# Rows.net
KiCad netlist of a schematic drawn in Altium Designer
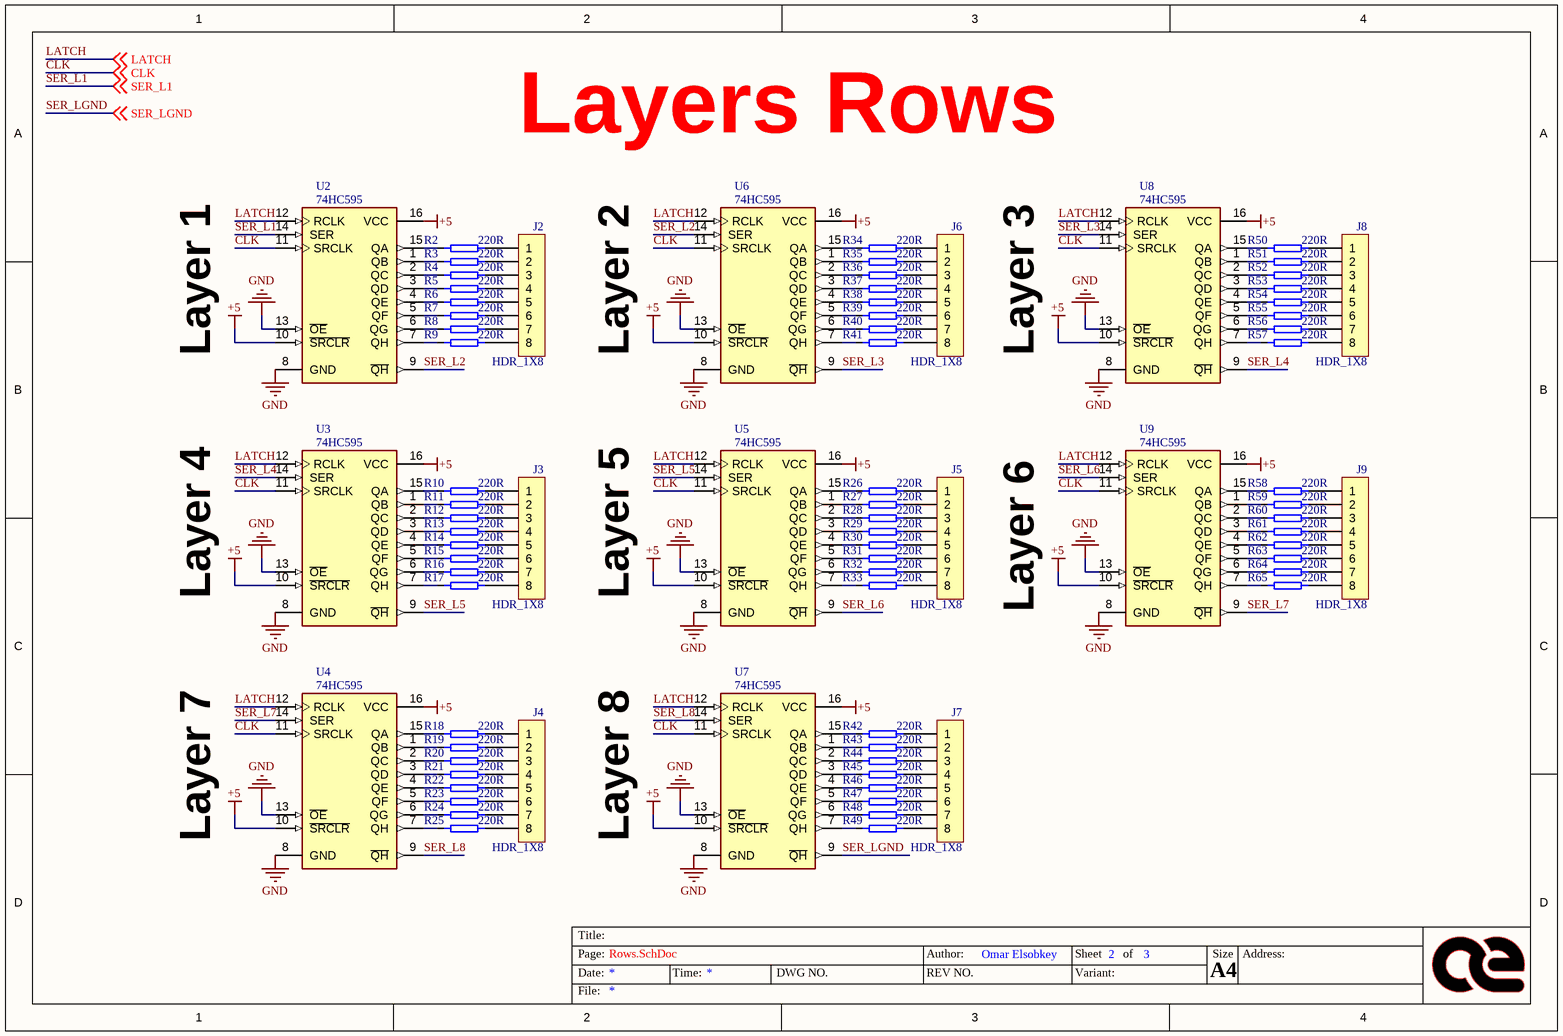
[diagram p0: Rows.SchDoc]

(export (version "E")
  (design (tool "Eeschema 10.0.6"))
  (components
    (comp (ref "J2")
      (value "HDR_1X8")
      (footprint "HDR_1X8_2.54MM")
      (description "Male Hedader 1x8")
      (libsource (lib "LED Cube") (part "HDR_1X8"))
    )
    (comp (ref "J3")
      (value "HDR_1X8")
      (footprint "HDR_1X8_2.54MM")
      (description "Male Hedader 1x8")
      (libsource (lib "LED Cube") (part "HDR_1X8"))
    )
    (comp (ref "J4")
      (value "HDR_1X8")
      (footprint "HDR_1X8_2.54MM")
      (description "Male Hedader 1x8")
      (libsource (lib "LED Cube") (part "HDR_1X8"))
    )
    (comp (ref "J5")
      (value "HDR_1X8")
      (footprint "HDR_1X8_2.54MM")
      (description "Male Hedader 1x8")
      (libsource (lib "LED Cube") (part "HDR_1X8"))
    )
    (comp (ref "J6")
      (value "HDR_1X8")
      (footprint "HDR_1X8_2.54MM")
      (description "Male Hedader 1x8")
      (libsource (lib "LED Cube") (part "HDR_1X8"))
    )
    (comp (ref "J7")
      (value "HDR_1X8")
      (footprint "HDR_1X8_2.54MM")
      (description "Male Hedader 1x8")
      (libsource (lib "LED Cube") (part "HDR_1X8"))
    )
    (comp (ref "J8")
      (value "HDR_1X8")
      (footprint "HDR_1X8_2.54MM")
      (description "Male Hedader 1x8")
      (libsource (lib "LED Cube") (part "HDR_1X8"))
    )
    (comp (ref "J9")
      (value "HDR_1X8")
      (footprint "HDR_1X8_2.54MM")
      (description "Male Hedader 1x8")
      (libsource (lib "LED Cube") (part "HDR_1X8"))
    )
    (comp (ref "R2") (value "220R") (footprint "R_AXIAL_0.3MM") (libsource (lib "LED Cube") (part "R 220")))
    (comp (ref "R3") (value "220R") (footprint "R_AXIAL_0.3MM") (libsource (lib "LED Cube") (part "R 220")))
    (comp (ref "R4") (value "220R") (footprint "R_AXIAL_0.3MM") (libsource (lib "LED Cube") (part "R 220")))
    (comp (ref "R5") (value "220R") (footprint "R_AXIAL_0.3MM") (libsource (lib "LED Cube") (part "R 220")))
    (comp (ref "R6") (value "220R") (footprint "R_AXIAL_0.3MM") (libsource (lib "LED Cube") (part "R 220")))
    (comp (ref "R7") (value "220R") (footprint "R_AXIAL_0.3MM") (libsource (lib "LED Cube") (part "R 220")))
    (comp (ref "R8") (value "220R") (footprint "R_AXIAL_0.3MM") (libsource (lib "LED Cube") (part "R 220")))
    (comp (ref "R9") (value "220R") (footprint "R_AXIAL_0.3MM") (libsource (lib "LED Cube") (part "R 220")))
    (comp (ref "R10") (value "220R") (footprint "R_AXIAL_0.3MM") (libsource (lib "LED Cube") (part "R 220")))
    (comp (ref "R11") (value "220R") (footprint "R_AXIAL_0.3MM") (libsource (lib "LED Cube") (part "R 220")))
    (comp (ref "R12") (value "220R") (footprint "R_AXIAL_0.3MM") (libsource (lib "LED Cube") (part "R 220")))
    (comp (ref "R13") (value "220R") (footprint "R_AXIAL_0.3MM") (libsource (lib "LED Cube") (part "R 220")))
    (comp (ref "R14") (value "220R") (footprint "R_AXIAL_0.3MM") (libsource (lib "LED Cube") (part "R 220")))
    (comp (ref "R15") (value "220R") (footprint "R_AXIAL_0.3MM") (libsource (lib "LED Cube") (part "R 220")))
    (comp (ref "R16") (value "220R") (footprint "R_AXIAL_0.3MM") (libsource (lib "LED Cube") (part "R 220")))
    (comp (ref "R17") (value "220R") (footprint "R_AXIAL_0.3MM") (libsource (lib "LED Cube") (part "R 220")))
    (comp (ref "R18") (value "220R") (footprint "R_AXIAL_0.3MM") (libsource (lib "LED Cube") (part "R 220")))
    (comp (ref "R19") (value "220R") (footprint "R_AXIAL_0.3MM") (libsource (lib "LED Cube") (part "R 220")))
    (comp (ref "R20") (value "220R") (footprint "R_AXIAL_0.3MM") (libsource (lib "LED Cube") (part "R 220")))
    (comp (ref "R21") (value "220R") (footprint "R_AXIAL_0.3MM") (libsource (lib "LED Cube") (part "R 220")))
    (comp (ref "R22") (value "220R") (footprint "R_AXIAL_0.3MM") (libsource (lib "LED Cube") (part "R 220")))
    (comp (ref "R23") (value "220R") (footprint "R_AXIAL_0.3MM") (libsource (lib "LED Cube") (part "R 220")))
    (comp (ref "R24") (value "220R") (footprint "R_AXIAL_0.3MM") (libsource (lib "LED Cube") (part "R 220")))
    (comp (ref "R25") (value "220R") (footprint "R_AXIAL_0.3MM") (libsource (lib "LED Cube") (part "R 220")))
    (comp (ref "R26") (value "220R") (footprint "R_AXIAL_0.3MM") (libsource (lib "LED Cube") (part "R 220")))
    (comp (ref "R27") (value "220R") (footprint "R_AXIAL_0.3MM") (libsource (lib "LED Cube") (part "R 220")))
    (comp (ref "R28") (value "220R") (footprint "R_AXIAL_0.3MM") (libsource (lib "LED Cube") (part "R 220")))
    (comp (ref "R29") (value "220R") (footprint "R_AXIAL_0.3MM") (libsource (lib "LED Cube") (part "R 220")))
    (comp (ref "R30") (value "220R") (footprint "R_AXIAL_0.3MM") (libsource (lib "LED Cube") (part "R 220")))
    (comp (ref "R31") (value "220R") (footprint "R_AXIAL_0.3MM") (libsource (lib "LED Cube") (part "R 220")))
    (comp (ref "R32") (value "220R") (footprint "R_AXIAL_0.3MM") (libsource (lib "LED Cube") (part "R 220")))
    (comp (ref "R33") (value "220R") (footprint "R_AXIAL_0.3MM") (libsource (lib "LED Cube") (part "R 220")))
    (comp (ref "R34") (value "220R") (footprint "R_AXIAL_0.3MM") (libsource (lib "LED Cube") (part "R 220")))
    (comp (ref "R35") (value "220R") (footprint "R_AXIAL_0.3MM") (libsource (lib "LED Cube") (part "R 220")))
    (comp (ref "R36") (value "220R") (footprint "R_AXIAL_0.3MM") (libsource (lib "LED Cube") (part "R 220")))
    (comp (ref "R37") (value "220R") (footprint "R_AXIAL_0.3MM") (libsource (lib "LED Cube") (part "R 220")))
    (comp (ref "R38") (value "220R") (footprint "R_AXIAL_0.3MM") (libsource (lib "LED Cube") (part "R 220")))
    (comp (ref "R39") (value "220R") (footprint "R_AXIAL_0.3MM") (libsource (lib "LED Cube") (part "R 220")))
    (comp (ref "R40") (value "220R") (footprint "R_AXIAL_0.3MM") (libsource (lib "LED Cube") (part "R 220")))
    (comp (ref "R41") (value "220R") (footprint "R_AXIAL_0.3MM") (libsource (lib "LED Cube") (part "R 220")))
    (comp (ref "R42") (value "220R") (footprint "R_AXIAL_0.3MM") (libsource (lib "LED Cube") (part "R 220")))
    (comp (ref "R43") (value "220R") (footprint "R_AXIAL_0.3MM") (libsource (lib "LED Cube") (part "R 220")))
    (comp (ref "R44") (value "220R") (footprint "R_AXIAL_0.3MM") (libsource (lib "LED Cube") (part "R 220")))
    (comp (ref "R45") (value "220R") (footprint "R_AXIAL_0.3MM") (libsource (lib "LED Cube") (part "R 220")))
    (comp (ref "R46") (value "220R") (footprint "R_AXIAL_0.3MM") (libsource (lib "LED Cube") (part "R 220")))
    (comp (ref "R47") (value "220R") (footprint "R_AXIAL_0.3MM") (libsource (lib "LED Cube") (part "R 220")))
    (comp (ref "R48") (value "220R") (footprint "R_AXIAL_0.3MM") (libsource (lib "LED Cube") (part "R 220")))
    (comp (ref "R49") (value "220R") (footprint "R_AXIAL_0.3MM") (libsource (lib "LED Cube") (part "R 220")))
    (comp (ref "R50") (value "220R") (footprint "R_AXIAL_0.3MM") (libsource (lib "LED Cube") (part "R 220")))
    (comp (ref "R51") (value "220R") (footprint "R_AXIAL_0.3MM") (libsource (lib "LED Cube") (part "R 220")))
    (comp (ref "R52") (value "220R") (footprint "R_AXIAL_0.3MM") (libsource (lib "LED Cube") (part "R 220")))
    (comp (ref "R53") (value "220R") (footprint "R_AXIAL_0.3MM") (libsource (lib "LED Cube") (part "R 220")))
    (comp (ref "R54") (value "220R") (footprint "R_AXIAL_0.3MM") (libsource (lib "LED Cube") (part "R 220")))
    (comp (ref "R55") (value "220R") (footprint "R_AXIAL_0.3MM") (libsource (lib "LED Cube") (part "R 220")))
    (comp (ref "R56") (value "220R") (footprint "R_AXIAL_0.3MM") (libsource (lib "LED Cube") (part "R 220")))
    (comp (ref "R57") (value "220R") (footprint "R_AXIAL_0.3MM") (libsource (lib "LED Cube") (part "R 220")))
    (comp (ref "R58") (value "220R") (footprint "R_AXIAL_0.3MM") (libsource (lib "LED Cube") (part "R 220")))
    (comp (ref "R59") (value "220R") (footprint "R_AXIAL_0.3MM") (libsource (lib "LED Cube") (part "R 220")))
    (comp (ref "R60") (value "220R") (footprint "R_AXIAL_0.3MM") (libsource (lib "LED Cube") (part "R 220")))
    (comp (ref "R61") (value "220R") (footprint "R_AXIAL_0.3MM") (libsource (lib "LED Cube") (part "R 220")))
    (comp (ref "R62") (value "220R") (footprint "R_AXIAL_0.3MM") (libsource (lib "LED Cube") (part "R 220")))
    (comp (ref "R63") (value "220R") (footprint "R_AXIAL_0.3MM") (libsource (lib "LED Cube") (part "R 220")))
    (comp (ref "R64") (value "220R") (footprint "R_AXIAL_0.3MM") (libsource (lib "LED Cube") (part "R 220")))
    (comp (ref "R65") (value "220R") (footprint "R_AXIAL_0.3MM") (libsource (lib "LED Cube") (part "R 220")))
    (comp (ref "U2")
      (value "74HC595")
      (footprint "DIP16")
      (description "Shift Register 74595")
      (fields (field (name "MP") "CD74HC595E"))
      (libsource (lib "LED Cube") (part "74HC595"))
    )
    (comp (ref "U3")
      (value "74HC595")
      (footprint "DIP16")
      (description "Shift Register 74595")
      (fields (field (name "MP") "CD74HC595E"))
      (libsource (lib "LED Cube") (part "74HC595"))
    )
    (comp (ref "U4")
      (value "74HC595")
      (footprint "DIP16")
      (description "Shift Register 74595")
      (fields (field (name "MP") "CD74HC595E"))
      (libsource (lib "LED Cube") (part "74HC595"))
    )
    (comp (ref "U5")
      (value "74HC595")
      (footprint "DIP16")
      (description "Shift Register 74595")
      (fields (field (name "MP") "CD74HC595E"))
      (libsource (lib "LED Cube") (part "74HC595"))
    )
    (comp (ref "U6")
      (value "74HC595")
      (footprint "DIP16")
      (description "Shift Register 74595")
      (fields (field (name "MP") "CD74HC595E"))
      (libsource (lib "LED Cube") (part "74HC595"))
    )
    (comp (ref "U7")
      (value "74HC595")
      (footprint "DIP16")
      (description "Shift Register 74595")
      (fields (field (name "MP") "CD74HC595E"))
      (libsource (lib "LED Cube") (part "74HC595"))
    )
    (comp (ref "U8")
      (value "74HC595")
      (footprint "DIP16")
      (description "Shift Register 74595")
      (fields (field (name "MP") "CD74HC595E"))
      (libsource (lib "LED Cube") (part "74HC595"))
    )
    (comp (ref "U9")
      (value "74HC595")
      (footprint "DIP16")
      (description "Shift Register 74595")
      (fields (field (name "MP") "CD74HC595E"))
      (libsource (lib "LED Cube") (part "74HC595"))
    )
  )
  (nets
    (net (code "1") (name "+5") (class "Default")
      (node (ref "U2") (pin "10") (pinfunction "~{SRCLR}_10") (pintype "input"))
      (node (ref "U2") (pin "16") (pinfunction "VCC_16") (pintype "power_in"))
      (node (ref "U3") (pin "10") (pinfunction "~{SRCLR}_10") (pintype "input"))
      (node (ref "U3") (pin "16") (pinfunction "VCC_16") (pintype "power_in"))
      (node (ref "U4") (pin "10") (pinfunction "~{SRCLR}_10") (pintype "input"))
      (node (ref "U4") (pin "16") (pinfunction "VCC_16") (pintype "power_in"))
      (node (ref "U5") (pin "10") (pinfunction "~{SRCLR}_10") (pintype "input"))
      (node (ref "U5") (pin "16") (pinfunction "VCC_16") (pintype "power_in"))
      (node (ref "U6") (pin "10") (pinfunction "~{SRCLR}_10") (pintype "input"))
      (node (ref "U6") (pin "16") (pinfunction "VCC_16") (pintype "power_in"))
      (node (ref "U7") (pin "10") (pinfunction "~{SRCLR}_10") (pintype "input"))
      (node (ref "U7") (pin "16") (pinfunction "VCC_16") (pintype "power_in"))
      (node (ref "U8") (pin "10") (pinfunction "~{SRCLR}_10") (pintype "input"))
      (node (ref "U8") (pin "16") (pinfunction "VCC_16") (pintype "power_in"))
      (node (ref "U9") (pin "10") (pinfunction "~{SRCLR}_10") (pintype "input"))
      (node (ref "U9") (pin "16") (pinfunction "VCC_16") (pintype "power_in"))
    )
    (net (code "2") (name "/SER_L2") (class "Default")
      (node (ref "U2") (pin "9") (pinfunction "~{QH}_9") (pintype "output"))
      (node (ref "U6") (pin "14") (pinfunction "SER_14") (pintype "input"))
    )
    (net (code "3") (name "/SER_L3") (class "Default")
      (node (ref "U6") (pin "9") (pinfunction "~{QH}_9") (pintype "output"))
      (node (ref "U8") (pin "14") (pinfunction "SER_14") (pintype "input"))
    )
    (net (code "4") (name "/SER_L4") (class "Default")
      (node (ref "U3") (pin "14") (pinfunction "SER_14") (pintype "input"))
      (node (ref "U8") (pin "9") (pinfunction "~{QH}_9") (pintype "output"))
    )
    (net (code "5") (name "/SER_L5") (class "Default")
      (node (ref "U3") (pin "9") (pinfunction "~{QH}_9") (pintype "output"))
      (node (ref "U5") (pin "14") (pinfunction "SER_14") (pintype "input"))
    )
    (net (code "6") (name "/SER_L6") (class "Default")
      (node (ref "U5") (pin "9") (pinfunction "~{QH}_9") (pintype "output"))
      (node (ref "U9") (pin "14") (pinfunction "SER_14") (pintype "input"))
    )
    (net (code "7") (name "/SER_L7") (class "Default")
      (node (ref "U4") (pin "14") (pinfunction "SER_14") (pintype "input"))
      (node (ref "U9") (pin "9") (pinfunction "~{QH}_9") (pintype "output"))
    )
    (net (code "8") (name "/SER_L8") (class "Default")
      (node (ref "U4") (pin "9") (pinfunction "~{QH}_9") (pintype "output"))
      (node (ref "U7") (pin "14") (pinfunction "SER_14") (pintype "input"))
    )
    (net (code "9") (name "CLK") (class "Default")
      (node (ref "U2") (pin "11") (pinfunction "SRCLK_11") (pintype "input"))
      (node (ref "U3") (pin "11") (pinfunction "SRCLK_11") (pintype "input"))
      (node (ref "U4") (pin "11") (pinfunction "SRCLK_11") (pintype "input"))
      (node (ref "U5") (pin "11") (pinfunction "SRCLK_11") (pintype "input"))
      (node (ref "U6") (pin "11") (pinfunction "SRCLK_11") (pintype "input"))
      (node (ref "U7") (pin "11") (pinfunction "SRCLK_11") (pintype "input"))
      (node (ref "U8") (pin "11") (pinfunction "SRCLK_11") (pintype "input"))
      (node (ref "U9") (pin "11") (pinfunction "SRCLK_11") (pintype "input"))
    )
    (net (code "10") (name "GND") (class "Default")
      (node (ref "U2") (pin "13") (pinfunction "~{OE}_13") (pintype "input"))
      (node (ref "U2") (pin "8") (pinfunction "GND_8") (pintype "power_in"))
      (node (ref "U3") (pin "13") (pinfunction "~{OE}_13") (pintype "input"))
      (node (ref "U3") (pin "8") (pinfunction "GND_8") (pintype "power_in"))
      (node (ref "U4") (pin "13") (pinfunction "~{OE}_13") (pintype "input"))
      (node (ref "U4") (pin "8") (pinfunction "GND_8") (pintype "power_in"))
      (node (ref "U5") (pin "13") (pinfunction "~{OE}_13") (pintype "input"))
      (node (ref "U5") (pin "8") (pinfunction "GND_8") (pintype "power_in"))
      (node (ref "U6") (pin "13") (pinfunction "~{OE}_13") (pintype "input"))
      (node (ref "U6") (pin "8") (pinfunction "GND_8") (pintype "power_in"))
      (node (ref "U7") (pin "13") (pinfunction "~{OE}_13") (pintype "input"))
      (node (ref "U7") (pin "8") (pinfunction "GND_8") (pintype "power_in"))
      (node (ref "U8") (pin "13") (pinfunction "~{OE}_13") (pintype "input"))
      (node (ref "U8") (pin "8") (pinfunction "GND_8") (pintype "power_in"))
      (node (ref "U9") (pin "13") (pinfunction "~{OE}_13") (pintype "input"))
      (node (ref "U9") (pin "8") (pinfunction "GND_8") (pintype "power_in"))
    )
    (net (code "11") (name "LATCH") (class "Default")
      (node (ref "U2") (pin "12") (pinfunction "RCLK_12") (pintype "input"))
      (node (ref "U3") (pin "12") (pinfunction "RCLK_12") (pintype "input"))
      (node (ref "U4") (pin "12") (pinfunction "RCLK_12") (pintype "input"))
      (node (ref "U5") (pin "12") (pinfunction "RCLK_12") (pintype "input"))
      (node (ref "U6") (pin "12") (pinfunction "RCLK_12") (pintype "input"))
      (node (ref "U7") (pin "12") (pinfunction "RCLK_12") (pintype "input"))
      (node (ref "U8") (pin "12") (pinfunction "RCLK_12") (pintype "input"))
      (node (ref "U9") (pin "12") (pinfunction "RCLK_12") (pintype "input"))
    )
    (net (code "12") (name "Net-(J2-Pad1)") (class "Default")
      (node (ref "J2") (pin "1") (pinfunction "1_1") (pintype "passive"))
      (node (ref "R2") (pin "2") (pinfunction "2_2") (pintype "passive"))
    )
    (net (code "13") (name "Net-(J2-Pad2)") (class "Default")
      (node (ref "J2") (pin "2") (pinfunction "2_2") (pintype "passive"))
      (node (ref "R3") (pin "2") (pinfunction "2_2") (pintype "passive"))
    )
    (net (code "14") (name "Net-(J2-Pad3)") (class "Default")
      (node (ref "J2") (pin "3") (pinfunction "3_3") (pintype "passive"))
      (node (ref "R4") (pin "2") (pinfunction "2_2") (pintype "passive"))
    )
    (net (code "15") (name "Net-(J2-Pad4)") (class "Default")
      (node (ref "J2") (pin "4") (pinfunction "4_4") (pintype "passive"))
      (node (ref "R5") (pin "2") (pinfunction "2_2") (pintype "passive"))
    )
    (net (code "16") (name "Net-(J2-Pad5)") (class "Default")
      (node (ref "J2") (pin "5") (pinfunction "5_5") (pintype "passive"))
      (node (ref "R6") (pin "2") (pinfunction "2_2") (pintype "passive"))
    )
    (net (code "17") (name "Net-(J2-Pad6)") (class "Default")
      (node (ref "J2") (pin "6") (pinfunction "6_6") (pintype "passive"))
      (node (ref "R7") (pin "2") (pinfunction "2_2") (pintype "passive"))
    )
    (net (code "18") (name "Net-(J2-Pad7)") (class "Default")
      (node (ref "J2") (pin "7") (pinfunction "7_7") (pintype "passive"))
      (node (ref "R8") (pin "2") (pinfunction "2_2") (pintype "passive"))
    )
    (net (code "19") (name "Net-(J2-Pad8)") (class "Default")
      (node (ref "J2") (pin "8") (pinfunction "8_8") (pintype "passive"))
      (node (ref "R9") (pin "2") (pinfunction "2_2") (pintype "passive"))
    )
    (net (code "20") (name "Net-(J3-Pad1)") (class "Default")
      (node (ref "J3") (pin "1") (pinfunction "1_1") (pintype "passive"))
      (node (ref "R10") (pin "2") (pinfunction "2_2") (pintype "passive"))
    )
    (net (code "21") (name "Net-(J3-Pad2)") (class "Default")
      (node (ref "J3") (pin "2") (pinfunction "2_2") (pintype "passive"))
      (node (ref "R11") (pin "2") (pinfunction "2_2") (pintype "passive"))
    )
    (net (code "22") (name "Net-(J3-Pad3)") (class "Default")
      (node (ref "J3") (pin "3") (pinfunction "3_3") (pintype "passive"))
      (node (ref "R12") (pin "2") (pinfunction "2_2") (pintype "passive"))
    )
    (net (code "23") (name "Net-(J3-Pad4)") (class "Default")
      (node (ref "J3") (pin "4") (pinfunction "4_4") (pintype "passive"))
      (node (ref "R13") (pin "2") (pinfunction "2_2") (pintype "passive"))
    )
    (net (code "24") (name "Net-(J3-Pad5)") (class "Default")
      (node (ref "J3") (pin "5") (pinfunction "5_5") (pintype "passive"))
      (node (ref "R14") (pin "2") (pinfunction "2_2") (pintype "passive"))
    )
    (net (code "25") (name "Net-(J3-Pad6)") (class "Default")
      (node (ref "J3") (pin "6") (pinfunction "6_6") (pintype "passive"))
      (node (ref "R15") (pin "2") (pinfunction "2_2") (pintype "passive"))
    )
    (net (code "26") (name "Net-(J3-Pad7)") (class "Default")
      (node (ref "J3") (pin "7") (pinfunction "7_7") (pintype "passive"))
      (node (ref "R16") (pin "2") (pinfunction "2_2") (pintype "passive"))
    )
    (net (code "27") (name "Net-(J3-Pad8)") (class "Default")
      (node (ref "J3") (pin "8") (pinfunction "8_8") (pintype "passive"))
      (node (ref "R17") (pin "2") (pinfunction "2_2") (pintype "passive"))
    )
    (net (code "28") (name "Net-(J4-Pad1)") (class "Default")
      (node (ref "J4") (pin "1") (pinfunction "1_1") (pintype "passive"))
      (node (ref "R18") (pin "2") (pinfunction "2_2") (pintype "passive"))
    )
    (net (code "29") (name "Net-(J4-Pad2)") (class "Default")
      (node (ref "J4") (pin "2") (pinfunction "2_2") (pintype "passive"))
      (node (ref "R19") (pin "2") (pinfunction "2_2") (pintype "passive"))
    )
    (net (code "30") (name "Net-(J4-Pad3)") (class "Default")
      (node (ref "J4") (pin "3") (pinfunction "3_3") (pintype "passive"))
      (node (ref "R20") (pin "2") (pinfunction "2_2") (pintype "passive"))
    )
    (net (code "31") (name "Net-(J4-Pad4)") (class "Default")
      (node (ref "J4") (pin "4") (pinfunction "4_4") (pintype "passive"))
      (node (ref "R21") (pin "2") (pinfunction "2_2") (pintype "passive"))
    )
    (net (code "32") (name "Net-(J4-Pad5)") (class "Default")
      (node (ref "J4") (pin "5") (pinfunction "5_5") (pintype "passive"))
      (node (ref "R22") (pin "2") (pinfunction "2_2") (pintype "passive"))
    )
    (net (code "33") (name "Net-(J4-Pad6)") (class "Default")
      (node (ref "J4") (pin "6") (pinfunction "6_6") (pintype "passive"))
      (node (ref "R23") (pin "2") (pinfunction "2_2") (pintype "passive"))
    )
    (net (code "34") (name "Net-(J4-Pad7)") (class "Default")
      (node (ref "J4") (pin "7") (pinfunction "7_7") (pintype "passive"))
      (node (ref "R24") (pin "2") (pinfunction "2_2") (pintype "passive"))
    )
    (net (code "35") (name "Net-(J4-Pad8)") (class "Default")
      (node (ref "J4") (pin "8") (pinfunction "8_8") (pintype "passive"))
      (node (ref "R25") (pin "2") (pinfunction "2_2") (pintype "passive"))
    )
    (net (code "36") (name "Net-(J5-Pad1)") (class "Default")
      (node (ref "J5") (pin "1") (pinfunction "1_1") (pintype "passive"))
      (node (ref "R26") (pin "2") (pinfunction "2_2") (pintype "passive"))
    )
    (net (code "37") (name "Net-(J5-Pad2)") (class "Default")
      (node (ref "J5") (pin "2") (pinfunction "2_2") (pintype "passive"))
      (node (ref "R27") (pin "2") (pinfunction "2_2") (pintype "passive"))
    )
    (net (code "38") (name "Net-(J5-Pad3)") (class "Default")
      (node (ref "J5") (pin "3") (pinfunction "3_3") (pintype "passive"))
      (node (ref "R28") (pin "2") (pinfunction "2_2") (pintype "passive"))
    )
    (net (code "39") (name "Net-(J5-Pad4)") (class "Default")
      (node (ref "J5") (pin "4") (pinfunction "4_4") (pintype "passive"))
      (node (ref "R29") (pin "2") (pinfunction "2_2") (pintype "passive"))
    )
    (net (code "40") (name "Net-(J5-Pad5)") (class "Default")
      (node (ref "J5") (pin "5") (pinfunction "5_5") (pintype "passive"))
      (node (ref "R30") (pin "2") (pinfunction "2_2") (pintype "passive"))
    )
    (net (code "41") (name "Net-(J5-Pad6)") (class "Default")
      (node (ref "J5") (pin "6") (pinfunction "6_6") (pintype "passive"))
      (node (ref "R31") (pin "2") (pinfunction "2_2") (pintype "passive"))
    )
    (net (code "42") (name "Net-(J5-Pad7)") (class "Default")
      (node (ref "J5") (pin "7") (pinfunction "7_7") (pintype "passive"))
      (node (ref "R32") (pin "2") (pinfunction "2_2") (pintype "passive"))
    )
    (net (code "43") (name "Net-(J5-Pad8)") (class "Default")
      (node (ref "J5") (pin "8") (pinfunction "8_8") (pintype "passive"))
      (node (ref "R33") (pin "2") (pinfunction "2_2") (pintype "passive"))
    )
    (net (code "44") (name "Net-(J6-Pad1)") (class "Default")
      (node (ref "J6") (pin "1") (pinfunction "1_1") (pintype "passive"))
      (node (ref "R34") (pin "2") (pinfunction "2_2") (pintype "passive"))
    )
    (net (code "45") (name "Net-(J6-Pad2)") (class "Default")
      (node (ref "J6") (pin "2") (pinfunction "2_2") (pintype "passive"))
      (node (ref "R35") (pin "2") (pinfunction "2_2") (pintype "passive"))
    )
    (net (code "46") (name "Net-(J6-Pad3)") (class "Default")
      (node (ref "J6") (pin "3") (pinfunction "3_3") (pintype "passive"))
      (node (ref "R36") (pin "2") (pinfunction "2_2") (pintype "passive"))
    )
    (net (code "47") (name "Net-(J6-Pad4)") (class "Default")
      (node (ref "J6") (pin "4") (pinfunction "4_4") (pintype "passive"))
      (node (ref "R37") (pin "2") (pinfunction "2_2") (pintype "passive"))
    )
    (net (code "48") (name "Net-(J6-Pad5)") (class "Default")
      (node (ref "J6") (pin "5") (pinfunction "5_5") (pintype "passive"))
      (node (ref "R38") (pin "2") (pinfunction "2_2") (pintype "passive"))
    )
    (net (code "49") (name "Net-(J6-Pad6)") (class "Default")
      (node (ref "J6") (pin "6") (pinfunction "6_6") (pintype "passive"))
      (node (ref "R39") (pin "2") (pinfunction "2_2") (pintype "passive"))
    )
    (net (code "50") (name "Net-(J6-Pad7)") (class "Default")
      (node (ref "J6") (pin "7") (pinfunction "7_7") (pintype "passive"))
      (node (ref "R40") (pin "2") (pinfunction "2_2") (pintype "passive"))
    )
    (net (code "51") (name "Net-(J6-Pad8)") (class "Default")
      (node (ref "J6") (pin "8") (pinfunction "8_8") (pintype "passive"))
      (node (ref "R41") (pin "2") (pinfunction "2_2") (pintype "passive"))
    )
    (net (code "52") (name "Net-(J7-Pad1)") (class "Default")
      (node (ref "J7") (pin "1") (pinfunction "1_1") (pintype "passive"))
      (node (ref "R42") (pin "2") (pinfunction "2_2") (pintype "passive"))
    )
    (net (code "53") (name "Net-(J7-Pad2)") (class "Default")
      (node (ref "J7") (pin "2") (pinfunction "2_2") (pintype "passive"))
      (node (ref "R43") (pin "2") (pinfunction "2_2") (pintype "passive"))
    )
    (net (code "54") (name "Net-(J7-Pad3)") (class "Default")
      (node (ref "J7") (pin "3") (pinfunction "3_3") (pintype "passive"))
      (node (ref "R44") (pin "2") (pinfunction "2_2") (pintype "passive"))
    )
    (net (code "55") (name "Net-(J7-Pad4)") (class "Default")
      (node (ref "J7") (pin "4") (pinfunction "4_4") (pintype "passive"))
      (node (ref "R45") (pin "2") (pinfunction "2_2") (pintype "passive"))
    )
    (net (code "56") (name "Net-(J7-Pad5)") (class "Default")
      (node (ref "J7") (pin "5") (pinfunction "5_5") (pintype "passive"))
      (node (ref "R46") (pin "2") (pinfunction "2_2") (pintype "passive"))
    )
    (net (code "57") (name "Net-(J7-Pad6)") (class "Default")
      (node (ref "J7") (pin "6") (pinfunction "6_6") (pintype "passive"))
      (node (ref "R47") (pin "2") (pinfunction "2_2") (pintype "passive"))
    )
    (net (code "58") (name "Net-(J7-Pad7)") (class "Default")
      (node (ref "J7") (pin "7") (pinfunction "7_7") (pintype "passive"))
      (node (ref "R48") (pin "2") (pinfunction "2_2") (pintype "passive"))
    )
    (net (code "59") (name "Net-(J7-Pad8)") (class "Default")
      (node (ref "J7") (pin "8") (pinfunction "8_8") (pintype "passive"))
      (node (ref "R49") (pin "2") (pinfunction "2_2") (pintype "passive"))
    )
    (net (code "60") (name "Net-(J8-Pad1)") (class "Default")
      (node (ref "J8") (pin "1") (pinfunction "1_1") (pintype "passive"))
      (node (ref "R50") (pin "2") (pinfunction "2_2") (pintype "passive"))
    )
    (net (code "61") (name "Net-(J8-Pad2)") (class "Default")
      (node (ref "J8") (pin "2") (pinfunction "2_2") (pintype "passive"))
      (node (ref "R51") (pin "2") (pinfunction "2_2") (pintype "passive"))
    )
    (net (code "62") (name "Net-(J8-Pad3)") (class "Default")
      (node (ref "J8") (pin "3") (pinfunction "3_3") (pintype "passive"))
      (node (ref "R52") (pin "2") (pinfunction "2_2") (pintype "passive"))
    )
    (net (code "63") (name "Net-(J8-Pad4)") (class "Default")
      (node (ref "J8") (pin "4") (pinfunction "4_4") (pintype "passive"))
      (node (ref "R53") (pin "2") (pinfunction "2_2") (pintype "passive"))
    )
    (net (code "64") (name "Net-(J8-Pad5)") (class "Default")
      (node (ref "J8") (pin "5") (pinfunction "5_5") (pintype "passive"))
      (node (ref "R54") (pin "2") (pinfunction "2_2") (pintype "passive"))
    )
    (net (code "65") (name "Net-(J8-Pad6)") (class "Default")
      (node (ref "J8") (pin "6") (pinfunction "6_6") (pintype "passive"))
      (node (ref "R55") (pin "2") (pinfunction "2_2") (pintype "passive"))
    )
    (net (code "66") (name "Net-(J8-Pad7)") (class "Default")
      (node (ref "J8") (pin "7") (pinfunction "7_7") (pintype "passive"))
      (node (ref "R56") (pin "2") (pinfunction "2_2") (pintype "passive"))
    )
    (net (code "67") (name "Net-(J8-Pad8)") (class "Default")
      (node (ref "J8") (pin "8") (pinfunction "8_8") (pintype "passive"))
      (node (ref "R57") (pin "2") (pinfunction "2_2") (pintype "passive"))
    )
    (net (code "68") (name "Net-(J9-Pad1)") (class "Default")
      (node (ref "J9") (pin "1") (pinfunction "1_1") (pintype "passive"))
      (node (ref "R58") (pin "2") (pinfunction "2_2") (pintype "passive"))
    )
    (net (code "69") (name "Net-(J9-Pad2)") (class "Default")
      (node (ref "J9") (pin "2") (pinfunction "2_2") (pintype "passive"))
      (node (ref "R59") (pin "2") (pinfunction "2_2") (pintype "passive"))
    )
    (net (code "70") (name "Net-(J9-Pad3)") (class "Default")
      (node (ref "J9") (pin "3") (pinfunction "3_3") (pintype "passive"))
      (node (ref "R60") (pin "2") (pinfunction "2_2") (pintype "passive"))
    )
    (net (code "71") (name "Net-(J9-Pad4)") (class "Default")
      (node (ref "J9") (pin "4") (pinfunction "4_4") (pintype "passive"))
      (node (ref "R61") (pin "2") (pinfunction "2_2") (pintype "passive"))
    )
    (net (code "72") (name "Net-(J9-Pad5)") (class "Default")
      (node (ref "J9") (pin "5") (pinfunction "5_5") (pintype "passive"))
      (node (ref "R62") (pin "2") (pinfunction "2_2") (pintype "passive"))
    )
    (net (code "73") (name "Net-(J9-Pad6)") (class "Default")
      (node (ref "J9") (pin "6") (pinfunction "6_6") (pintype "passive"))
      (node (ref "R63") (pin "2") (pinfunction "2_2") (pintype "passive"))
    )
    (net (code "74") (name "Net-(J9-Pad7)") (class "Default")
      (node (ref "J9") (pin "7") (pinfunction "7_7") (pintype "passive"))
      (node (ref "R64") (pin "2") (pinfunction "2_2") (pintype "passive"))
    )
    (net (code "75") (name "Net-(J9-Pad8)") (class "Default")
      (node (ref "J9") (pin "8") (pinfunction "8_8") (pintype "passive"))
      (node (ref "R65") (pin "2") (pinfunction "2_2") (pintype "passive"))
    )
    (net (code "76") (name "Net-(U2-QA)") (class "Default")
      (node (ref "R2") (pin "1") (pinfunction "1_1") (pintype "passive"))
      (node (ref "U2") (pin "15") (pinfunction "QA_15") (pintype "output"))
    )
    (net (code "77") (name "Net-(U2-QB)") (class "Default")
      (node (ref "R3") (pin "1") (pinfunction "1_1") (pintype "passive"))
      (node (ref "U2") (pin "1") (pinfunction "QB_1") (pintype "output"))
    )
    (net (code "78") (name "Net-(U2-QC)") (class "Default")
      (node (ref "R4") (pin "1") (pinfunction "1_1") (pintype "passive"))
      (node (ref "U2") (pin "2") (pinfunction "QC_2") (pintype "output"))
    )
    (net (code "79") (name "Net-(U2-QD)") (class "Default")
      (node (ref "R5") (pin "1") (pinfunction "1_1") (pintype "passive"))
      (node (ref "U2") (pin "3") (pinfunction "QD_3") (pintype "output"))
    )
    (net (code "80") (name "Net-(U2-QE)") (class "Default")
      (node (ref "R6") (pin "1") (pinfunction "1_1") (pintype "passive"))
      (node (ref "U2") (pin "4") (pinfunction "QE_4") (pintype "output"))
    )
    (net (code "81") (name "Net-(U2-QF)") (class "Default")
      (node (ref "R7") (pin "1") (pinfunction "1_1") (pintype "passive"))
      (node (ref "U2") (pin "5") (pinfunction "QF_5") (pintype "output"))
    )
    (net (code "82") (name "Net-(U2-QG)") (class "Default")
      (node (ref "R8") (pin "1") (pinfunction "1_1") (pintype "passive"))
      (node (ref "U2") (pin "6") (pinfunction "QG_6") (pintype "output"))
    )
    (net (code "83") (name "Net-(U2-QH)") (class "Default")
      (node (ref "R9") (pin "1") (pinfunction "1_1") (pintype "passive"))
      (node (ref "U2") (pin "7") (pinfunction "QH_7") (pintype "output"))
    )
    (net (code "84") (name "Net-(U3-QA)") (class "Default")
      (node (ref "R10") (pin "1") (pinfunction "1_1") (pintype "passive"))
      (node (ref "U3") (pin "15") (pinfunction "QA_15") (pintype "output"))
    )
    (net (code "85") (name "Net-(U3-QB)") (class "Default")
      (node (ref "R11") (pin "1") (pinfunction "1_1") (pintype "passive"))
      (node (ref "U3") (pin "1") (pinfunction "QB_1") (pintype "output"))
    )
    (net (code "86") (name "Net-(U3-QC)") (class "Default")
      (node (ref "R12") (pin "1") (pinfunction "1_1") (pintype "passive"))
      (node (ref "U3") (pin "2") (pinfunction "QC_2") (pintype "output"))
    )
    (net (code "87") (name "Net-(U3-QD)") (class "Default")
      (node (ref "R13") (pin "1") (pinfunction "1_1") (pintype "passive"))
      (node (ref "U3") (pin "3") (pinfunction "QD_3") (pintype "output"))
    )
    (net (code "88") (name "Net-(U3-QE)") (class "Default")
      (node (ref "R14") (pin "1") (pinfunction "1_1") (pintype "passive"))
      (node (ref "U3") (pin "4") (pinfunction "QE_4") (pintype "output"))
    )
    (net (code "89") (name "Net-(U3-QF)") (class "Default")
      (node (ref "R15") (pin "1") (pinfunction "1_1") (pintype "passive"))
      (node (ref "U3") (pin "5") (pinfunction "QF_5") (pintype "output"))
    )
    (net (code "90") (name "Net-(U3-QG)") (class "Default")
      (node (ref "R16") (pin "1") (pinfunction "1_1") (pintype "passive"))
      (node (ref "U3") (pin "6") (pinfunction "QG_6") (pintype "output"))
    )
    (net (code "91") (name "Net-(U3-QH)") (class "Default")
      (node (ref "R17") (pin "1") (pinfunction "1_1") (pintype "passive"))
      (node (ref "U3") (pin "7") (pinfunction "QH_7") (pintype "output"))
    )
    (net (code "92") (name "Net-(U4-QA)") (class "Default")
      (node (ref "R18") (pin "1") (pinfunction "1_1") (pintype "passive"))
      (node (ref "U4") (pin "15") (pinfunction "QA_15") (pintype "output"))
    )
    (net (code "93") (name "Net-(U4-QB)") (class "Default")
      (node (ref "R19") (pin "1") (pinfunction "1_1") (pintype "passive"))
      (node (ref "U4") (pin "1") (pinfunction "QB_1") (pintype "output"))
    )
    (net (code "94") (name "Net-(U4-QC)") (class "Default")
      (node (ref "R20") (pin "1") (pinfunction "1_1") (pintype "passive"))
      (node (ref "U4") (pin "2") (pinfunction "QC_2") (pintype "output"))
    )
    (net (code "95") (name "Net-(U4-QD)") (class "Default")
      (node (ref "R21") (pin "1") (pinfunction "1_1") (pintype "passive"))
      (node (ref "U4") (pin "3") (pinfunction "QD_3") (pintype "output"))
    )
    (net (code "96") (name "Net-(U4-QE)") (class "Default")
      (node (ref "R22") (pin "1") (pinfunction "1_1") (pintype "passive"))
      (node (ref "U4") (pin "4") (pinfunction "QE_4") (pintype "output"))
    )
    (net (code "97") (name "Net-(U4-QF)") (class "Default")
      (node (ref "R23") (pin "1") (pinfunction "1_1") (pintype "passive"))
      (node (ref "U4") (pin "5") (pinfunction "QF_5") (pintype "output"))
    )
    (net (code "98") (name "Net-(U4-QG)") (class "Default")
      (node (ref "R24") (pin "1") (pinfunction "1_1") (pintype "passive"))
      (node (ref "U4") (pin "6") (pinfunction "QG_6") (pintype "output"))
    )
    (net (code "99") (name "Net-(U4-QH)") (class "Default")
      (node (ref "R25") (pin "1") (pinfunction "1_1") (pintype "passive"))
      (node (ref "U4") (pin "7") (pinfunction "QH_7") (pintype "output"))
    )
    (net (code "100") (name "Net-(U5-QA)") (class "Default")
      (node (ref "R26") (pin "1") (pinfunction "1_1") (pintype "passive"))
      (node (ref "U5") (pin "15") (pinfunction "QA_15") (pintype "output"))
    )
    (net (code "101") (name "Net-(U5-QB)") (class "Default")
      (node (ref "R27") (pin "1") (pinfunction "1_1") (pintype "passive"))
      (node (ref "U5") (pin "1") (pinfunction "QB_1") (pintype "output"))
    )
    (net (code "102") (name "Net-(U5-QC)") (class "Default")
      (node (ref "R28") (pin "1") (pinfunction "1_1") (pintype "passive"))
      (node (ref "U5") (pin "2") (pinfunction "QC_2") (pintype "output"))
    )
    (net (code "103") (name "Net-(U5-QD)") (class "Default")
      (node (ref "R29") (pin "1") (pinfunction "1_1") (pintype "passive"))
      (node (ref "U5") (pin "3") (pinfunction "QD_3") (pintype "output"))
    )
    (net (code "104") (name "Net-(U5-QE)") (class "Default")
      (node (ref "R30") (pin "1") (pinfunction "1_1") (pintype "passive"))
      (node (ref "U5") (pin "4") (pinfunction "QE_4") (pintype "output"))
    )
    (net (code "105") (name "Net-(U5-QF)") (class "Default")
      (node (ref "R31") (pin "1") (pinfunction "1_1") (pintype "passive"))
      (node (ref "U5") (pin "5") (pinfunction "QF_5") (pintype "output"))
    )
    (net (code "106") (name "Net-(U5-QG)") (class "Default")
      (node (ref "R32") (pin "1") (pinfunction "1_1") (pintype "passive"))
      (node (ref "U5") (pin "6") (pinfunction "QG_6") (pintype "output"))
    )
    (net (code "107") (name "Net-(U5-QH)") (class "Default")
      (node (ref "R33") (pin "1") (pinfunction "1_1") (pintype "passive"))
      (node (ref "U5") (pin "7") (pinfunction "QH_7") (pintype "output"))
    )
    (net (code "108") (name "Net-(U6-QA)") (class "Default")
      (node (ref "R34") (pin "1") (pinfunction "1_1") (pintype "passive"))
      (node (ref "U6") (pin "15") (pinfunction "QA_15") (pintype "output"))
    )
    (net (code "109") (name "Net-(U6-QB)") (class "Default")
      (node (ref "R35") (pin "1") (pinfunction "1_1") (pintype "passive"))
      (node (ref "U6") (pin "1") (pinfunction "QB_1") (pintype "output"))
    )
    (net (code "110") (name "Net-(U6-QC)") (class "Default")
      (node (ref "R36") (pin "1") (pinfunction "1_1") (pintype "passive"))
      (node (ref "U6") (pin "2") (pinfunction "QC_2") (pintype "output"))
    )
    (net (code "111") (name "Net-(U6-QD)") (class "Default")
      (node (ref "R37") (pin "1") (pinfunction "1_1") (pintype "passive"))
      (node (ref "U6") (pin "3") (pinfunction "QD_3") (pintype "output"))
    )
    (net (code "112") (name "Net-(U6-QE)") (class "Default")
      (node (ref "R38") (pin "1") (pinfunction "1_1") (pintype "passive"))
      (node (ref "U6") (pin "4") (pinfunction "QE_4") (pintype "output"))
    )
    (net (code "113") (name "Net-(U6-QF)") (class "Default")
      (node (ref "R39") (pin "1") (pinfunction "1_1") (pintype "passive"))
      (node (ref "U6") (pin "5") (pinfunction "QF_5") (pintype "output"))
    )
    (net (code "114") (name "Net-(U6-QG)") (class "Default")
      (node (ref "R40") (pin "1") (pinfunction "1_1") (pintype "passive"))
      (node (ref "U6") (pin "6") (pinfunction "QG_6") (pintype "output"))
    )
    (net (code "115") (name "Net-(U6-QH)") (class "Default")
      (node (ref "R41") (pin "1") (pinfunction "1_1") (pintype "passive"))
      (node (ref "U6") (pin "7") (pinfunction "QH_7") (pintype "output"))
    )
    (net (code "116") (name "Net-(U7-QA)") (class "Default")
      (node (ref "R42") (pin "1") (pinfunction "1_1") (pintype "passive"))
      (node (ref "U7") (pin "15") (pinfunction "QA_15") (pintype "output"))
    )
    (net (code "117") (name "Net-(U7-QB)") (class "Default")
      (node (ref "R43") (pin "1") (pinfunction "1_1") (pintype "passive"))
      (node (ref "U7") (pin "1") (pinfunction "QB_1") (pintype "output"))
    )
    (net (code "118") (name "Net-(U7-QC)") (class "Default")
      (node (ref "R44") (pin "1") (pinfunction "1_1") (pintype "passive"))
      (node (ref "U7") (pin "2") (pinfunction "QC_2") (pintype "output"))
    )
    (net (code "119") (name "Net-(U7-QD)") (class "Default")
      (node (ref "R45") (pin "1") (pinfunction "1_1") (pintype "passive"))
      (node (ref "U7") (pin "3") (pinfunction "QD_3") (pintype "output"))
    )
    (net (code "120") (name "Net-(U7-QE)") (class "Default")
      (node (ref "R46") (pin "1") (pinfunction "1_1") (pintype "passive"))
      (node (ref "U7") (pin "4") (pinfunction "QE_4") (pintype "output"))
    )
    (net (code "121") (name "Net-(U7-QF)") (class "Default")
      (node (ref "R47") (pin "1") (pinfunction "1_1") (pintype "passive"))
      (node (ref "U7") (pin "5") (pinfunction "QF_5") (pintype "output"))
    )
    (net (code "122") (name "Net-(U7-QG)") (class "Default")
      (node (ref "R48") (pin "1") (pinfunction "1_1") (pintype "passive"))
      (node (ref "U7") (pin "6") (pinfunction "QG_6") (pintype "output"))
    )
    (net (code "123") (name "Net-(U7-QH)") (class "Default")
      (node (ref "R49") (pin "1") (pinfunction "1_1") (pintype "passive"))
      (node (ref "U7") (pin "7") (pinfunction "QH_7") (pintype "output"))
    )
    (net (code "124") (name "Net-(U8-QA)") (class "Default")
      (node (ref "R50") (pin "1") (pinfunction "1_1") (pintype "passive"))
      (node (ref "U8") (pin "15") (pinfunction "QA_15") (pintype "output"))
    )
    (net (code "125") (name "Net-(U8-QB)") (class "Default")
      (node (ref "R51") (pin "1") (pinfunction "1_1") (pintype "passive"))
      (node (ref "U8") (pin "1") (pinfunction "QB_1") (pintype "output"))
    )
    (net (code "126") (name "Net-(U8-QC)") (class "Default")
      (node (ref "R52") (pin "1") (pinfunction "1_1") (pintype "passive"))
      (node (ref "U8") (pin "2") (pinfunction "QC_2") (pintype "output"))
    )
    (net (code "127") (name "Net-(U8-QD)") (class "Default")
      (node (ref "R53") (pin "1") (pinfunction "1_1") (pintype "passive"))
      (node (ref "U8") (pin "3") (pinfunction "QD_3") (pintype "output"))
    )
    (net (code "128") (name "Net-(U8-QE)") (class "Default")
      (node (ref "R54") (pin "1") (pinfunction "1_1") (pintype "passive"))
      (node (ref "U8") (pin "4") (pinfunction "QE_4") (pintype "output"))
    )
    (net (code "129") (name "Net-(U8-QF)") (class "Default")
      (node (ref "R55") (pin "1") (pinfunction "1_1") (pintype "passive"))
      (node (ref "U8") (pin "5") (pinfunction "QF_5") (pintype "output"))
    )
    (net (code "130") (name "Net-(U8-QG)") (class "Default")
      (node (ref "R56") (pin "1") (pinfunction "1_1") (pintype "passive"))
      (node (ref "U8") (pin "6") (pinfunction "QG_6") (pintype "output"))
    )
    (net (code "131") (name "Net-(U8-QH)") (class "Default")
      (node (ref "R57") (pin "1") (pinfunction "1_1") (pintype "passive"))
      (node (ref "U8") (pin "7") (pinfunction "QH_7") (pintype "output"))
    )
    (net (code "132") (name "Net-(U9-QA)") (class "Default")
      (node (ref "R58") (pin "1") (pinfunction "1_1") (pintype "passive"))
      (node (ref "U9") (pin "15") (pinfunction "QA_15") (pintype "output"))
    )
    (net (code "133") (name "Net-(U9-QB)") (class "Default")
      (node (ref "R59") (pin "1") (pinfunction "1_1") (pintype "passive"))
      (node (ref "U9") (pin "1") (pinfunction "QB_1") (pintype "output"))
    )
    (net (code "134") (name "Net-(U9-QC)") (class "Default")
      (node (ref "R60") (pin "1") (pinfunction "1_1") (pintype "passive"))
      (node (ref "U9") (pin "2") (pinfunction "QC_2") (pintype "output"))
    )
    (net (code "135") (name "Net-(U9-QD)") (class "Default")
      (node (ref "R61") (pin "1") (pinfunction "1_1") (pintype "passive"))
      (node (ref "U9") (pin "3") (pinfunction "QD_3") (pintype "output"))
    )
    (net (code "136") (name "Net-(U9-QE)") (class "Default")
      (node (ref "R62") (pin "1") (pinfunction "1_1") (pintype "passive"))
      (node (ref "U9") (pin "4") (pinfunction "QE_4") (pintype "output"))
    )
    (net (code "137") (name "Net-(U9-QF)") (class "Default")
      (node (ref "R63") (pin "1") (pinfunction "1_1") (pintype "passive"))
      (node (ref "U9") (pin "5") (pinfunction "QF_5") (pintype "output"))
    )
    (net (code "138") (name "Net-(U9-QG)") (class "Default")
      (node (ref "R64") (pin "1") (pinfunction "1_1") (pintype "passive"))
      (node (ref "U9") (pin "6") (pinfunction "QG_6") (pintype "output"))
    )
    (net (code "139") (name "Net-(U9-QH)") (class "Default")
      (node (ref "R65") (pin "1") (pinfunction "1_1") (pintype "passive"))
      (node (ref "U9") (pin "7") (pinfunction "QH_7") (pintype "output"))
    )
    (net (code "140") (name "SER_L1") (class "Default")
      (node (ref "U2") (pin "14") (pinfunction "SER_14") (pintype "input"))
    )
    (net (code "141") (name "SER_LGND") (class "Default")
      (node (ref "U7") (pin "9") (pinfunction "~{QH}_9") (pintype "output"))
    )
  )
)
